# osu_keyboard.net
KiCad netlist of a schematic drawn in Altium Designer
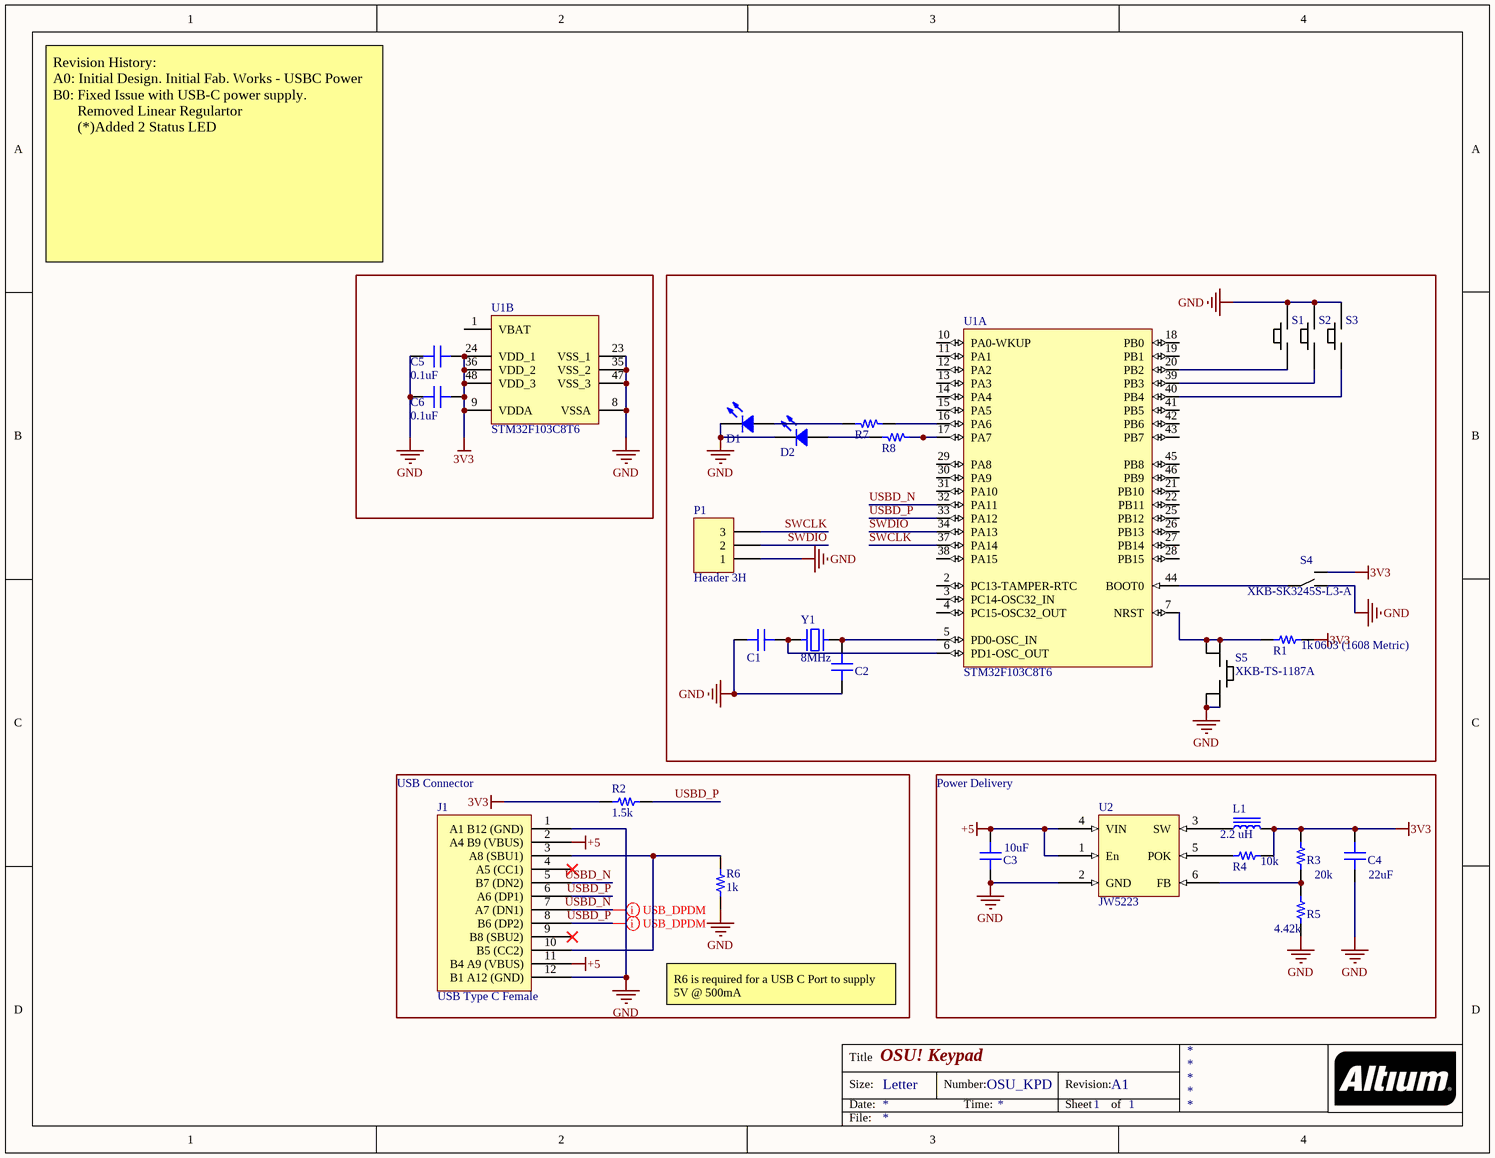
[diagram p0: osu_keyboard.SchDoc]

(export (version "E")
  (design (tool "Eeschema 10.0.6"))
  (components
    (comp (ref "C1")
      (value "22pF")
      (footprint "CAP 0603/1608")
      (description "CAP CER 22PF 50V C0G 0603")
      (fields
        (field (name "PART NUMBER") "C1608C0G1H220J080AA")
        (field (name "MANUFACTURER") "TDK Corporation")
      )
      (libsource (lib "Celestial Library Database") (part "Capacitor"))
    )
    (comp (ref "C2")
      (value "22pF")
      (footprint "CAP 0603/1608")
      (description "CAP CER 22PF 50V C0G 0603")
      (fields
        (field (name "PART NUMBER") "C1608C0G1H220J080AA")
        (field (name "MANUFACTURER") "TDK Corporation")
      )
      (libsource (lib "Celestial Library Database") (part "Capacitor"))
    )
    (comp (ref "C3")
      (value "10uF")
      (footprint "CAP 0805/2012")
      (description "CAP CER 10UF 6.3V X5R 0805")
      (fields
        (field (name "PART NUMBER") "C2012X5R0J106K125AB")
        (field (name "MANUFACTURER") "TDK Corporation")
      )
      (libsource (lib "Celestial Library Database") (part "Capacitor"))
    )
    (comp (ref "C4")
      (value "22uF")
      (footprint "CAP 0805/2012")
      (description "CAP CER 22UF 6.3V X5R 0805")
      (fields (field (name "PART NUMBER") "C0805C226M9PACTU") (field (name "MANUFACTURER") "Kemet"))
      (libsource (lib "Celestial Library Database") (part "Capacitor"))
    )
    (comp (ref "C5")
      (value "0.1uF")
      (footprint "CAP 0603/1608")
      (description "CAP CER 0.1UF 25V X7R 0603")
      (fields
        (field (name "PART NUMBER") "C1608X7R1E104K080AA")
        (field (name "MANUFACTURER") "TDK Corporation")
      )
      (libsource (lib "Celestial Library Database") (part "Capacitor"))
    )
    (comp (ref "C6")
      (value "0.1uF")
      (footprint "CAP 0603/1608")
      (description "CAP CER 0.1UF 25V X7R 0603")
      (fields
        (field (name "PART NUMBER") "C1608X7R1E104K080AA")
        (field (name "MANUFACTURER") "TDK Corporation")
      )
      (libsource (lib "Celestial Library Database") (part "Capacitor"))
    )
    (comp (ref "D1")
      (value "Green")
      (footprint "LED 0805/2012 GREEN")
      (description "LED GREEN CLEAR 0805 SMD")
      (fields (field (name "PART NUMBER") "LTST-C171KGKT") (field (name "MANUFACTURER") "Lite-On Inc."))
      (libsource (lib "Celestial Library Database") (part "LED"))
    )
    (comp (ref "D2")
      (value "Blue")
      (footprint "LED 0805/2012 BLUE")
      (description "LED BLUE CLEAR 0805 SMD")
      (fields (field (name "PART NUMBER") "LTST-C171TBKT") (field (name "MANUFACTURER") "Lite-On Inc."))
      (libsource (lib "Celestial Library Database") (part "LED"))
    )
    (comp (ref "J1")
      (value "USB Type C Female")
      (footprint "USB Type C Female")
      (libsource (lib "OSU_KBD_SCHLIB") (part "USB Type C Female"))
    )
    (comp (ref "L1")
      (value "2.2 uH")
      (footprint "INDP1722X10N")
      (description "Inductor 2.2uH")
      (libsource (lib "OSU_KBD_SCHLIB") (part "UHP252010NF"))
    )
    (comp (ref "P1")
      (value "Header 3H")
      (footprint "HDR1X3H")
      (description "Header, 3-Pin, Right Angle")
      (fields (field (name "PUBLISHER") "Altium Limited"))
      (libsource (lib "Miscellaneous Connectors") (part "Header 3H"))
    )
    (comp (ref "R1")
      (value "1k")
      (footprint "RES 0603/1608")
      (description "RES SMD 1K OHM 1% 1/10W 0603")
      (fields
        (field (name "PART NUMBER") "ERJ-3EKF1001V")
        (field (name "MANUFACTURER") "Panasonic Electronic Components")
        (field (name "DEVICE PACKAGE") "0603 (1608 Metric)")
      )
      (libsource (lib "Celestial Library Database") (part "Resistor"))
    )
    (comp (ref "R2")
      (value "1.5k")
      (footprint "RES 0603/1608")
      (description "RES SMD 1.5KOHM 0.05% 1/10W 0603")
      (fields
        (field (name "PART NUMBER") "ERA-3ARW152V")
        (field (name "MANUFACTURER") "Panasonic Electronic Components")
      )
      (libsource (lib "Celestial Library Database") (part "Resistor"))
    )
    (comp (ref "R3")
      (value "20k")
      (footprint "RES 0805/2012")
      (description "RES SMD 20K OHM 0.1% 1/8W 0805")
      (fields
        (field (name "PART NUMBER") "ERA-6AEB203V")
        (field (name "MANUFACTURER") "Panasonic Electronic Components")
      )
      (libsource (lib "Celestial Library Database") (part "Resistor"))
    )
    (comp (ref "R4")
      (value "10k")
      (footprint "RES 0805/2012")
      (description "RES SMD 10K OHM 0.1% 1/8W 0805")
      (fields
        (field (name "PART NUMBER") "ERA-6AEB103V")
        (field (name "MANUFACTURER") "Panasonic Electronic Components")
      )
      (libsource (lib "Celestial Library Database") (part "Resistor"))
    )
    (comp (ref "R5")
      (value "4.42k")
      (footprint "RES 0805/2012")
      (description "RES SMD 4.42K OHM 0.1% 1/8W 0805")
      (fields
        (field (name "PART NUMBER") "ERA-6AEB4421V")
        (field (name "MANUFACTURER") "Panasonic Electronic Components")
      )
      (libsource (lib "Celestial Library Database") (part "Resistor"))
    )
    (comp (ref "R6")
      (value "1k")
      (footprint "RES 0603/1608")
      (description "RES SMD 1K OHM 1% 1/10W 0603")
      (fields
        (field (name "PART NUMBER") "ERJ-3EKF1001V")
        (field (name "MANUFACTURER") "Panasonic Electronic Components")
      )
      (libsource (lib "Celestial Library Database") (part "Resistor"))
    )
    (comp (ref "R7")
      (value "330")
      (footprint "RES 0603/1608")
      (description "RES SMD 330 OHM 1% 1/4W 0603")
      (fields
        (field (name "PART NUMBER") "ERJ-PA3F3300V")
        (field (name "MANUFACTURER") "Panasonic Electronic Components")
      )
      (libsource (lib "Celestial Library Database") (part "Resistor"))
    )
    (comp (ref "R8")
      (value "330")
      (footprint "RES 0603/1608")
      (description "RES SMD 330 OHM 1% 1/4W 0603")
      (fields
        (field (name "PART NUMBER") "ERJ-PA3F3300V")
        (field (name "MANUFACTURER") "Panasonic Electronic Components")
      )
      (libsource (lib "Celestial Library Database") (part "Resistor"))
    )
    (comp (ref "S1")
      (value "CherryMXSwitch")
      (footprint "CherryMX")
      (description "CherryMX Switch")
      (libsource (lib "OSU_KBD_SCHLIB") (part "CherryMXSwitch"))
    )
    (comp (ref "S2")
      (value "CherryMXSwitch")
      (footprint "CherryMX")
      (description "CherryMX Switch")
      (libsource (lib "OSU_KBD_SCHLIB") (part "CherryMXSwitch"))
    )
    (comp (ref "S3")
      (value "CherryMXSwitch")
      (footprint "CherryMX")
      (description "CherryMX Switch")
      (libsource (lib "OSU_KBD_SCHLIB") (part "CherryMXSwitch"))
    )
    (comp (ref "S4")
      (value "XKB-SK3245S-L3-A")
      (footprint "XKB-SK-3245S")
      (description "Toggle Switch")
      (libsource (lib "OSU_KBD_SCHLIB") (part "XKB-SK3245S-L3-A"))
    )
    (comp (ref "S5")
      (value "XKB-TS-1187A")
      (footprint "XKB-RS-1187A")
      (description "Push Button")
      (libsource (lib "OSU_KBD_SCHLIB") (part "XKB-TS-1187A"))
    )
    (comp (ref "U1")
      (value "STM32F103C8T6")
      (footprint "STM-LQFP48_N")
      (libsource (lib "STMicroelectronics STM32 F1") (part "STM32F103C8T6"))
    )
    (comp (ref "U2")
      (value "JW5223")
      (footprint "SOT23-6N")
      (description "SMPS Buck")
      (libsource (lib "OSU_KBD_SCHLIB") (part "JW5223"))
    )
    (comp (ref "Y1")
      (value "8MHz")
      (footprint "TAXM_SMD_CRYSTAL")
      (libsource (lib "OSU_KBD_SCHLIB") (part "TAXM8M4RDBCCT2T"))
    )
  )
  (nets
    (net (code "1") (name "+5") (class "Default")
      (node (ref "C3") (pin "2") (pinfunction "2_2") (pintype "passive"))
      (node (ref "J1") (pin "11") (pinfunction "B4_A9_(VBUS)_11") (pintype "passive"))
      (node (ref "J1") (pin "2") (pinfunction "A4_B9_(VBUS)_2") (pintype "passive"))
      (node (ref "U2") (pin "1") (pinfunction "En_1") (pintype "input"))
      (node (ref "U2") (pin "4") (pinfunction "VIN_4") (pintype "input"))
    )
    (net (code "2") (name "/SWCLK") (class "Default")
      (node (ref "P1") (pin "3") (pinfunction "3_3") (pintype "passive"))
      (node (ref "U1") (pin "37") (pinfunction "PA14_37") (pintype "bidirectional"))
    )
    (net (code "3") (name "/SWDIO") (class "Default")
      (node (ref "P1") (pin "2") (pinfunction "2_2") (pintype "passive"))
      (node (ref "U1") (pin "34") (pinfunction "PA13_34") (pintype "bidirectional"))
    )
    (net (code "4") (name "/USBD_N") (class "Default")
      (node (ref "J1") (pin "5") (pinfunction "B7_(DN2)_5") (pintype "passive"))
      (node (ref "J1") (pin "7") (pinfunction "A7_(DN1)_7") (pintype "passive"))
      (node (ref "U1") (pin "32") (pinfunction "PA11_32") (pintype "bidirectional"))
    )
    (net (code "5") (name "/USBD_P") (class "Default")
      (node (ref "J1") (pin "6") (pinfunction "A6_(DP1)_6") (pintype "passive"))
      (node (ref "J1") (pin "8") (pinfunction "B6_(DP2)_8") (pintype "passive"))
      (node (ref "R2") (pin "1") (pinfunction "1_1") (pintype "passive"))
      (node (ref "U1") (pin "33") (pinfunction "PA12_33") (pintype "bidirectional"))
    )
    (net (code "6") (name "3V3") (class "Default")
      (node (ref "C4") (pin "2") (pinfunction "2_2") (pintype "passive"))
      (node (ref "C5") (pin "2") (pinfunction "2_2") (pintype "passive"))
      (node (ref "C6") (pin "2") (pinfunction "2_2") (pintype "passive"))
      (node (ref "L1") (pin "2") (pinfunction "2_2") (pintype "passive"))
      (node (ref "R1") (pin "2") (pinfunction "2_2") (pintype "passive"))
      (node (ref "R2") (pin "2") (pinfunction "2_2") (pintype "passive"))
      (node (ref "R3") (pin "1") (pinfunction "1_1") (pintype "passive"))
      (node (ref "R4") (pin "2") (pinfunction "2_2") (pintype "passive"))
      (node (ref "S4") (pin "1") (pinfunction "1_1") (pintype "passive"))
      (node (ref "U1") (pin "24") (pinfunction "VDD_1_24") (pintype "power_in"))
      (node (ref "U1") (pin "36") (pinfunction "VDD_2_36") (pintype "power_in"))
      (node (ref "U1") (pin "48") (pinfunction "VDD_3_48") (pintype "power_in"))
      (node (ref "U1") (pin "9") (pinfunction "VDDA_9") (pintype "power_in"))
    )
    (net (code "7") (name "GND") (class "Default")
      (node (ref "C1") (pin "1") (pinfunction "1_1") (pintype "passive"))
      (node (ref "C2") (pin "2") (pinfunction "2_2") (pintype "passive"))
      (node (ref "C3") (pin "1") (pinfunction "1_1") (pintype "passive"))
      (node (ref "C4") (pin "1") (pinfunction "1_1") (pintype "passive"))
      (node (ref "C5") (pin "1") (pinfunction "1_1") (pintype "passive"))
      (node (ref "C6") (pin "1") (pinfunction "1_1") (pintype "passive"))
      (node (ref "D1") (pin "2") (pinfunction "2_2") (pintype "passive"))
      (node (ref "D2") (pin "2") (pinfunction "2_2") (pintype "passive"))
      (node (ref "J1") (pin "1") (pinfunction "A1_B12_(GND)_1") (pintype "passive"))
      (node (ref "J1") (pin "12") (pinfunction "B1_A12_(GND)_12") (pintype "passive"))
      (node (ref "P1") (pin "1") (pinfunction "1_1") (pintype "passive"))
      (node (ref "R5") (pin "1") (pinfunction "1_1") (pintype "passive"))
      (node (ref "R6") (pin "2") (pinfunction "2_2") (pintype "passive"))
      (node (ref "S1") (pin "2") (pinfunction "2_2") (pintype "passive"))
      (node (ref "S2") (pin "2") (pinfunction "2_2") (pintype "passive"))
      (node (ref "S3") (pin "2") (pinfunction "2_2") (pintype "passive"))
      (node (ref "S4") (pin "3") (pinfunction "3_3") (pintype "passive"))
      (node (ref "S5") (pin "3") (pinfunction "3_3") (pintype "passive"))
      (node (ref "S5") (pin "4") (pinfunction "4_4") (pintype "passive"))
      (node (ref "U1") (pin "23") (pinfunction "VSS_1_23") (pintype "power_in"))
      (node (ref "U1") (pin "35") (pinfunction "VSS_2_35") (pintype "power_in"))
      (node (ref "U1") (pin "47") (pinfunction "VSS_3_47") (pintype "power_in"))
      (node (ref "U1") (pin "8") (pinfunction "VSSA_8") (pintype "power_in"))
      (node (ref "U2") (pin "2") (pinfunction "GND_2") (pintype "input"))
    )
    (net (code "8") (name "Net-(D1-Pad1)") (class "Default")
      (node (ref "D1") (pin "1") (pinfunction "1_1") (pintype "passive"))
      (node (ref "R7") (pin "2") (pinfunction "2_2") (pintype "passive"))
    )
    (net (code "9") (name "Net-(D2-Pad1)") (class "Default")
      (node (ref "D2") (pin "1") (pinfunction "1_1") (pintype "passive"))
      (node (ref "R8") (pin "2") (pinfunction "2_2") (pintype "passive"))
    )
    (net (code "10") (name "Net-(J1-A8_(SBU1))") (class "Default")
      (node (ref "J1") (pin "10") (pinfunction "B5_(CC2)_10") (pintype "passive"))
      (node (ref "J1") (pin "3") (pinfunction "A8_(SBU1)_3") (pintype "passive"))
      (node (ref "R6") (pin "1") (pinfunction "1_1") (pintype "passive"))
    )
    (net (code "11") (name "Net-(S4-0)") (class "Default")
      (node (ref "S4") (pin "2") (pinfunction "0_2") (pintype "passive"))
      (node (ref "U1") (pin "44") (pinfunction "BOOT0_44") (pintype "input"))
    )
    (net (code "12") (name "Net-(U1A-NRST)") (class "Default")
      (node (ref "R1") (pin "1") (pinfunction "1_1") (pintype "passive"))
      (node (ref "S5") (pin "1") (pinfunction "1_1") (pintype "passive"))
      (node (ref "S5") (pin "2") (pinfunction "2_2") (pintype "passive"))
      (node (ref "U1") (pin "7") (pinfunction "NRST_7") (pintype "bidirectional"))
    )
    (net (code "13") (name "Net-(U1A-PA6)") (class "Default")
      (node (ref "R7") (pin "1") (pinfunction "1_1") (pintype "passive"))
      (node (ref "U1") (pin "16") (pinfunction "PA6_16") (pintype "bidirectional"))
    )
    (net (code "14") (name "Net-(U1A-PA7)") (class "Default")
      (node (ref "R8") (pin "1") (pinfunction "1_1") (pintype "passive"))
      (node (ref "U1") (pin "17") (pinfunction "PA7_17") (pintype "bidirectional"))
    )
    (net (code "15") (name "Net-(U1A-PB2)") (class "Default")
      (node (ref "S1") (pin "1") (pinfunction "1_1") (pintype "passive"))
      (node (ref "U1") (pin "20") (pinfunction "PB2_20") (pintype "bidirectional"))
    )
    (net (code "16") (name "Net-(U1A-PB3)") (class "Default")
      (node (ref "S2") (pin "1") (pinfunction "1_1") (pintype "passive"))
      (node (ref "U1") (pin "39") (pinfunction "PB3_39") (pintype "bidirectional"))
    )
    (net (code "17") (name "Net-(U1A-PB4)") (class "Default")
      (node (ref "S3") (pin "1") (pinfunction "1_1") (pintype "passive"))
      (node (ref "U1") (pin "40") (pinfunction "PB4_40") (pintype "bidirectional"))
    )
    (net (code "18") (name "Net-(U1A-PD0-OSC_IN)") (class "Default")
      (node (ref "C2") (pin "1") (pinfunction "1_1") (pintype "passive"))
      (node (ref "U1") (pin "5") (pinfunction "PD0-OSC_IN_5") (pintype "bidirectional"))
      (node (ref "Y1") (pin "3") (pinfunction "3_3") (pintype "passive"))
    )
    (net (code "19") (name "Net-(U1A-PD1-OSC_OUT)") (class "Default")
      (node (ref "C1") (pin "2") (pinfunction "2_2") (pintype "passive"))
      (node (ref "U1") (pin "6") (pinfunction "PD1-OSC_OUT_6") (pintype "bidirectional"))
      (node (ref "Y1") (pin "1") (pinfunction "1_1") (pintype "passive"))
    )
    (net (code "20") (name "Net-(U2-FB)") (class "Default")
      (node (ref "R3") (pin "2") (pinfunction "2_2") (pintype "passive"))
      (node (ref "R5") (pin "2") (pinfunction "2_2") (pintype "passive"))
      (node (ref "U2") (pin "6") (pinfunction "FB_6") (pintype "input"))
    )
    (net (code "21") (name "Net-(U2-POK)") (class "Default")
      (node (ref "R4") (pin "1") (pinfunction "1_1") (pintype "passive"))
      (node (ref "U2") (pin "5") (pinfunction "POK_5") (pintype "input"))
    )
    (net (code "22") (name "Net-(U2-SW)") (class "Default")
      (node (ref "L1") (pin "1") (pinfunction "1_1") (pintype "passive"))
      (node (ref "U2") (pin "3") (pinfunction "SW_3") (pintype "input"))
    )
    (net (code "23") (name "unconnected-(J1-A5_(CC1)-Pad4)") (class "Default")
      (node (ref "J1") (pin "4") (pinfunction "A5_(CC1)_4") (pintype "passive+no_connect"))
    )
    (net (code "24") (name "unconnected-(J1-B8_(SBU2)-Pad9)") (class "Default")
      (node (ref "J1") (pin "9") (pinfunction "B8_(SBU2)_9") (pintype "passive+no_connect"))
    )
    (net (code "25") (name "unconnected-(U1A-PA0-WKUP-Pad10)") (class "Default")
      (node (ref "U1") (pin "10") (pinfunction "PA0-WKUP_10") (pintype "bidirectional"))
    )
    (net (code "26") (name "unconnected-(U1A-PA1-Pad11)") (class "Default")
      (node (ref "U1") (pin "11") (pinfunction "PA1_11") (pintype "bidirectional"))
    )
    (net (code "27") (name "unconnected-(U1A-PA2-Pad12)") (class "Default")
      (node (ref "U1") (pin "12") (pinfunction "PA2_12") (pintype "bidirectional"))
    )
    (net (code "28") (name "unconnected-(U1A-PA3-Pad13)") (class "Default")
      (node (ref "U1") (pin "13") (pinfunction "PA3_13") (pintype "bidirectional"))
    )
    (net (code "29") (name "unconnected-(U1A-PA4-Pad14)") (class "Default")
      (node (ref "U1") (pin "14") (pinfunction "PA4_14") (pintype "bidirectional"))
    )
    (net (code "30") (name "unconnected-(U1A-PA5-Pad15)") (class "Default")
      (node (ref "U1") (pin "15") (pinfunction "PA5_15") (pintype "bidirectional"))
    )
    (net (code "31") (name "unconnected-(U1A-PA8-Pad29)") (class "Default")
      (node (ref "U1") (pin "29") (pinfunction "PA8_29") (pintype "bidirectional"))
    )
    (net (code "32") (name "unconnected-(U1A-PA9-Pad30)") (class "Default")
      (node (ref "U1") (pin "30") (pinfunction "PA9_30") (pintype "bidirectional"))
    )
    (net (code "33") (name "unconnected-(U1A-PA10-Pad31)") (class "Default")
      (node (ref "U1") (pin "31") (pinfunction "PA10_31") (pintype "bidirectional"))
    )
    (net (code "34") (name "unconnected-(U1A-PA15-Pad38)") (class "Default")
      (node (ref "U1") (pin "38") (pinfunction "PA15_38") (pintype "bidirectional"))
    )
    (net (code "35") (name "unconnected-(U1A-PB0-Pad18)") (class "Default")
      (node (ref "U1") (pin "18") (pinfunction "PB0_18") (pintype "bidirectional"))
    )
    (net (code "36") (name "unconnected-(U1A-PB1-Pad19)") (class "Default")
      (node (ref "U1") (pin "19") (pinfunction "PB1_19") (pintype "bidirectional"))
    )
    (net (code "37") (name "unconnected-(U1A-PB5-Pad41)") (class "Default")
      (node (ref "U1") (pin "41") (pinfunction "PB5_41") (pintype "bidirectional"))
    )
    (net (code "38") (name "unconnected-(U1A-PB6-Pad42)") (class "Default")
      (node (ref "U1") (pin "42") (pinfunction "PB6_42") (pintype "bidirectional"))
    )
    (net (code "39") (name "unconnected-(U1A-PB7-Pad43)") (class "Default")
      (node (ref "U1") (pin "43") (pinfunction "PB7_43") (pintype "bidirectional"))
    )
    (net (code "40") (name "unconnected-(U1A-PB8-Pad45)") (class "Default")
      (node (ref "U1") (pin "45") (pinfunction "PB8_45") (pintype "bidirectional"))
    )
    (net (code "41") (name "unconnected-(U1A-PB9-Pad46)") (class "Default")
      (node (ref "U1") (pin "46") (pinfunction "PB9_46") (pintype "bidirectional"))
    )
    (net (code "42") (name "unconnected-(U1A-PB10-Pad21)") (class "Default")
      (node (ref "U1") (pin "21") (pinfunction "PB10_21") (pintype "bidirectional"))
    )
    (net (code "43") (name "unconnected-(U1A-PB11-Pad22)") (class "Default")
      (node (ref "U1") (pin "22") (pinfunction "PB11_22") (pintype "bidirectional"))
    )
    (net (code "44") (name "unconnected-(U1A-PB12-Pad25)") (class "Default")
      (node (ref "U1") (pin "25") (pinfunction "PB12_25") (pintype "bidirectional"))
    )
    (net (code "45") (name "unconnected-(U1A-PB13-Pad26)") (class "Default")
      (node (ref "U1") (pin "26") (pinfunction "PB13_26") (pintype "bidirectional"))
    )
    (net (code "46") (name "unconnected-(U1A-PB14-Pad27)") (class "Default")
      (node (ref "U1") (pin "27") (pinfunction "PB14_27") (pintype "bidirectional"))
    )
    (net (code "47") (name "unconnected-(U1A-PB15-Pad28)") (class "Default")
      (node (ref "U1") (pin "28") (pinfunction "PB15_28") (pintype "bidirectional"))
    )
    (net (code "48") (name "unconnected-(U1A-PC13-TAMPER-RTC-Pad2)") (class "Default")
      (node (ref "U1") (pin "2") (pinfunction "PC13-TAMPER-RTC_2") (pintype "bidirectional"))
    )
    (net (code "49") (name "unconnected-(U1A-PC14-OSC32_IN-Pad3)") (class "Default")
      (node (ref "U1") (pin "3") (pinfunction "PC14-OSC32_IN_3") (pintype "bidirectional"))
    )
    (net (code "50") (name "unconnected-(U1A-PC15-OSC32_OUT-Pad4)") (class "Default")
      (node (ref "U1") (pin "4") (pinfunction "PC15-OSC32_OUT_4") (pintype "bidirectional"))
    )
    (net (code "51") (name "unconnected-(U1B-VBAT-Pad1)") (class "Default")
      (node (ref "U1") (pin "1") (pinfunction "VBAT_1") (pintype "power_in"))
    )
  )
)
